# STM32F042G6.net
KiCad netlist of a schematic drawn in Altium Designer
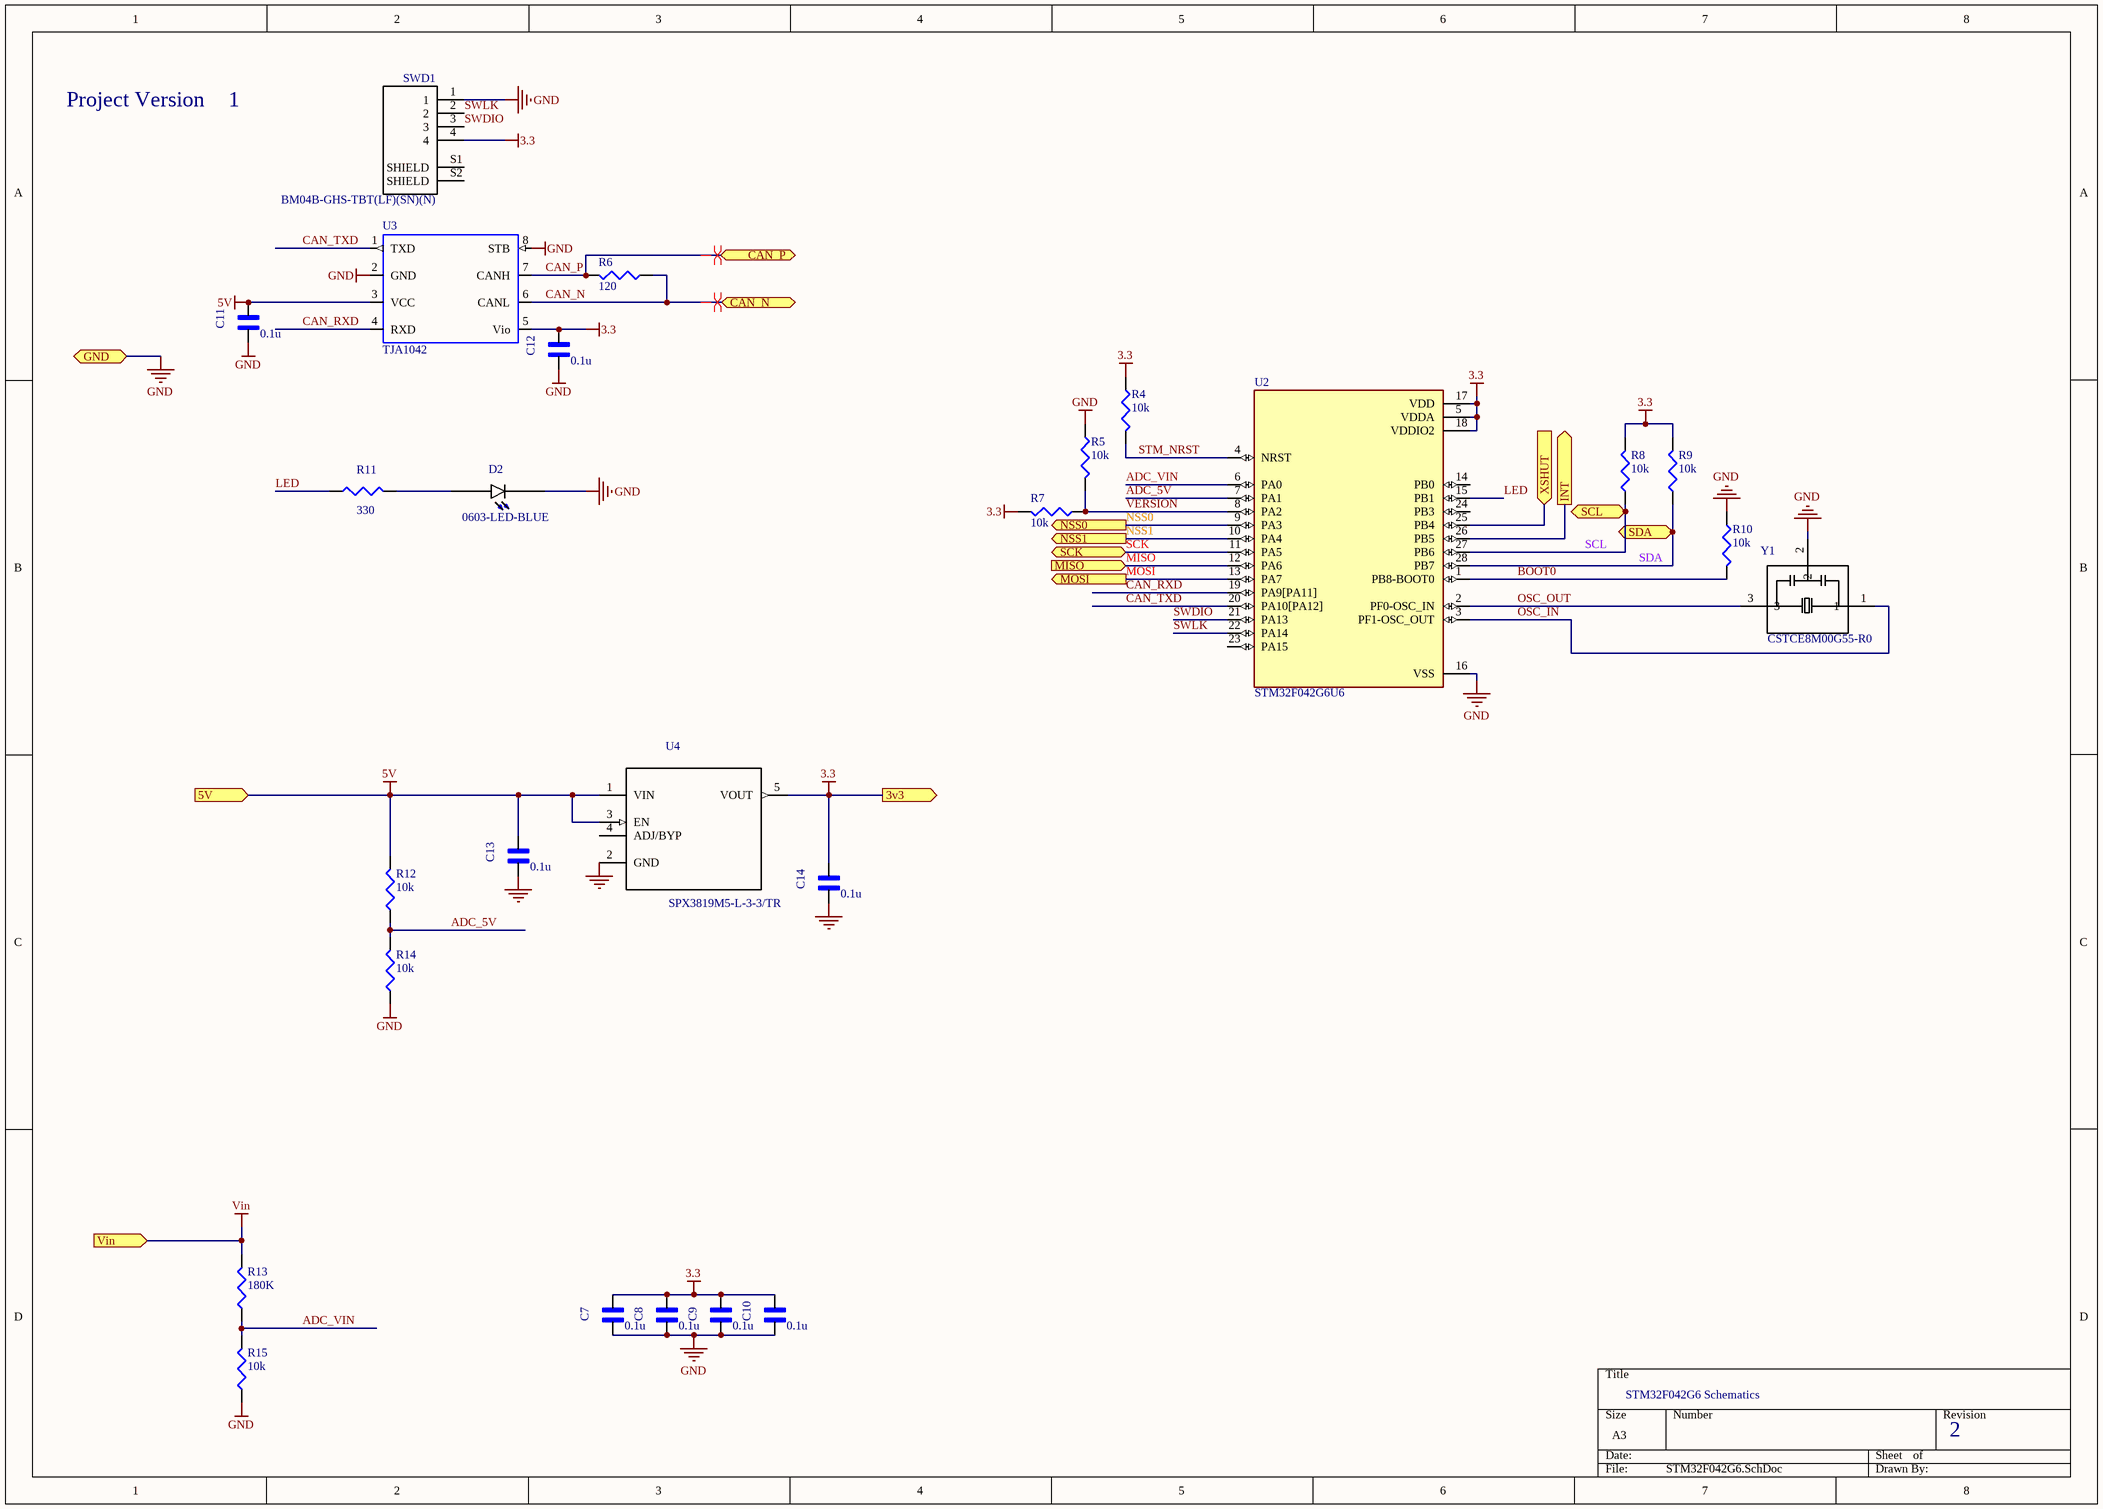
[diagram p0: STM32F042G6.SchDoc]

(export (version "E")
  (design (tool "Eeschema 10.0.6"))
  (components
    (comp (ref "C7")
      (value "0.1u")
      (footprint "*CAPC1608X90")
      (description "Cap Thin Film 0.1uf 50v 0603")
      (fields (field (name "MF") "AVX") (field (name "MP") "GX035C104MAT2-500 or CL10B104JB8NNNC"))
      (libsource (lib "lib") (part "GX035C104MAT2-500"))
    )
    (comp (ref "C8")
      (value "0.1u")
      (footprint "*CAPC1608X90")
      (description "Cap Thin Film 0.1uf 50v 0603")
      (fields (field (name "MF") "AVX") (field (name "MP") "GX035C104MAT2-500 or CL10B104JB8NNNC"))
      (libsource (lib "lib") (part "GX035C104MAT2-500"))
    )
    (comp (ref "C9")
      (value "0.1u")
      (footprint "*CAPC1608X90")
      (description "Cap Thin Film 0.1uf 50v 0603")
      (fields (field (name "MF") "AVX") (field (name "MP") "GX035C104MAT2-500 or CL10B104JB8NNNC"))
      (libsource (lib "lib") (part "GX035C104MAT2-500"))
    )
    (comp (ref "C10")
      (value "0.1u")
      (footprint "*CAPC1608X90")
      (description "Cap Thin Film 0.1uf 50v 0603")
      (fields (field (name "MF") "AVX") (field (name "MP") "GX035C104MAT2-500 or CL10B104JB8NNNC"))
      (libsource (lib "lib") (part "GX035C104MAT2-500"))
    )
    (comp (ref "C11")
      (value "0.1u")
      (footprint "*CAPC1608X90")
      (description "Cap Thin Film 0.1uf 50v 0603")
      (fields (field (name "MF") "AVX") (field (name "MP") "GX035C104MAT2-500 or CL10B104JB8NNNC"))
      (libsource (lib "lib") (part "GX035C104MAT2-500"))
    )
    (comp (ref "C12")
      (value "0.1u")
      (footprint "*CAPC1608X90")
      (description "Cap Thin Film 0.1uf 50v 0603")
      (fields (field (name "MF") "AVX") (field (name "MP") "GX035C104MAT2-500 or CL10B104JB8NNNC"))
      (libsource (lib "lib") (part "GX035C104MAT2-500"))
    )
    (comp (ref "C13")
      (value "0.1u")
      (footprint "*CAPC1608X90")
      (description "Cap Thin Film 0.1uf 50v 0603")
      (fields (field (name "MF") "AVX") (field (name "MP") "GX035C104MAT2-500"))
      (libsource (lib "lib") (part "GX035C104MAT2-500"))
    )
    (comp (ref "C14")
      (value "0.1u")
      (footprint "*CAPC1608X90")
      (description "Cap Thin Film 0.1uf 50v 0603")
      (fields (field (name "MF") "AVX") (field (name "MP") "GX035C104MAT2-500"))
      (libsource (lib "lib") (part "GX035C104MAT2-500"))
    )
    (comp (ref "D2")
      (value "0603-LED-BLUE")
      (footprint "*LEDM1608X80_LTE-C1906R-14(Primary)")
      (description "LED IrLED Chip LED 2-Pin SMD T/R")
      (libsource (lib "lib") (part "LTE-C1906R-14"))
    )
    (comp (ref "R4")
      (value "10k")
      (footprint "J1-0603")
      (description "10 kOhms 1 0.1 W 1 10 W Chip Resistor 0603 1608 Metric Thick Film")
      (fields (field (name "MF") "Yageo or NXP") (field (name "MP") "10K 1% 0603"))
      (libsource (lib "CAN_NODE_MINI") (part "RC0603FR-0710KL"))
    )
    (comp (ref "R5")
      (value "10k")
      (footprint "J1-0603")
      (description "10 kOhms 1 0.1 W 1 10 W Chip Resistor 0603 1608 Metric Thick Film")
      (fields (field (name "MF") "Yageo or NXP") (field (name "MP") "10K 1% 0603"))
      (libsource (lib "CAN_NODE_MINI") (part "RC0603FR-0710KL"))
    )
    (comp (ref "R6")
      (value "120")
      (footprint "J1-0603")
      (description "120 Ohms 1 0.1 W 1 10 W Chip Resistor 0603 1608 Metric Thick Film")
      (fields (field (name "MP") "RC0603FR-07120RL") (field (name "Comment") "Res3"))
      (libsource (lib "Miscellaneous Devices") (part "Res3"))
    )
    (comp (ref "R7")
      (value "10k")
      (footprint "J1-0603")
      (description "10 kOhms 1 0.1 W 1 10 W Chip Resistor 0603 1608 Metric Thick Film")
      (fields (field (name "MF") "Yageo or NXP") (field (name "MP") "10K 1% 0603"))
      (libsource (lib "CAN_NODE_MINI") (part "RC0603FR-0710KL"))
    )
    (comp (ref "R8")
      (value "10k")
      (footprint "J1-0603")
      (description "10 kOhms 1 0.1 W 1 10 W Chip Resistor 0603 1608 Metric Thick Film")
      (fields (field (name "MF") "Yageo or NXP") (field (name "MP") "10K 1% 0603"))
      (libsource (lib "CAN_NODE_MINI") (part "RC0603FR-0710KL"))
    )
    (comp (ref "R9")
      (value "10k")
      (footprint "J1-0603")
      (description "10 kOhms 1 0.1 W 1 10 W Chip Resistor 0603 1608 Metric Thick Film")
      (fields (field (name "MF") "Yageo or NXP") (field (name "MP") "10K 1% 0603"))
      (libsource (lib "CAN_NODE_MINI") (part "RC0603FR-0710KL"))
    )
    (comp (ref "R10")
      (value "10k")
      (footprint "J1-0603")
      (description "10 kOhms 1 0.1 W 1 10 W Chip Resistor 0603 1608 Metric Thick Film")
      (fields (field (name "MF") "Yageo or NXP") (field (name "MP") "10K 1% 0603"))
      (libsource (lib "CAN_NODE_MINI") (part "RC0603FR-0710KL"))
    )
    (comp (ref "R11")
      (value "330")
      (footprint "J1-0603")
      (description "Resistor")
      (fields (field (name "MP") "RC0603FR-07330RL") (field (name "Comment") "Res3"))
      (libsource (lib "Miscellaneous Devices") (part "Res3"))
    )
    (comp (ref "R12")
      (value "10k")
      (footprint "J1-0603")
      (description "10 kOhms 1 0.1 W 1 10 W Chip Resistor 0603 1608 Metric Thick Film")
      (fields (field (name "MF") "Yageo or NXP") (field (name "MP") "10K 1% 0603"))
      (libsource (lib "CAN_NODE_MINI") (part "RC0603FR-0710KL"))
    )
    (comp (ref "R13")
      (value "180K")
      (footprint "J1-0603")
      (description "10 kOhms 1 0.1 W 1 10 W Chip Resistor 0603 1608 Metric Thick Film")
      (fields (field (name "MF") "Yageo or NXP") (field (name "MP") "10K 1% 0603"))
      (libsource (lib "CAN_NODE_MINI") (part "RC0603FR-0710KL"))
    )
    (comp (ref "R14")
      (value "10k")
      (footprint "J1-0603")
      (description "10 kOhms 1 0.1 W 1 10 W Chip Resistor 0603 1608 Metric Thick Film")
      (fields (field (name "MF") "Yageo or NXP") (field (name "MP") "10K 1% 0603"))
      (libsource (lib "CAN_NODE_MINI") (part "RC0603FR-0710KL"))
    )
    (comp (ref "R15")
      (value "10k")
      (footprint "J1-0603")
      (description "10 kOhms 1 0.1 W 1 10 W Chip Resistor 0603 1608 Metric Thick Film")
      (fields (field (name "MF") "Yageo or NXP") (field (name "MP") "10K 1% 0603"))
      (libsource (lib "CAN_NODE_MINI") (part "RC0603FR-0710KL"))
    )
    (comp (ref "SWD1")
      (value "BM04B-GHS-TBT(LF)(SN)(N)")
      (footprint "JST_PAD")
      (description "Conn Shrouded Header HDR 4 POS 1.25mm Solder ST SMD Reel")
      (fields (field (name "MF") "JST Sales") (field (name "MP") "SM04B-GHS-TB(LF)(SN)"))
      (libsource (lib "lib") (part "BM04B-GHS-TBT(LF)(SN)(N)"))
    )
    (comp (ref "U2")
      (value "STM32F042G6U6")
      (footprint "STM32F042G6U6_UFQFPN4x4")
      (description "ARMÂ® CortexÂ®-M0 STM32F0 Microcontroller IC 32-Bit 48MHz 32KB _32K x 8_ FLASH 28-UFQFPN _4x4_")
      (fields (field (name "MF") "STMicroelectronics") (field (name "DESIGNER") "Ehsan Shaghaei"))
      (libsource (lib "lib") (part "STM32F042G6U6"))
    )
    (comp (ref "U3")
      (value "TJA1042")
      (footprint "SOT782-1")
      (description "1/1 Transceiver Half CANbus 8-SO")
      (fields (field (name "MF") "NXP USA"))
      (libsource (lib "lib") (part "TJA1042"))
    )
    (comp (ref "U4")
      (value "SPX3819M5-L-3-3/TR")
      (footprint "*SOT95P280X145-5N")
      (description "Low Dropout Voltage Regulator, Adjustable 0.5A, В±1%, 2.5 to 16 Vin, 5-Pin SOT-23")
      (fields (field (name "MF") "MaxLinear, Inc."))
      (libsource (lib "DC_DC") (part "SPX3819M5-L"))
    )
    (comp (ref "Y1")
      (value "CSTCE8M00G55-R0")
      (footprint "*OSC_CSTCE8M00G55-R0")
      (description "Ceramic Resonator 8MHz ??0.5% _Tol_ ??0.2% _Stability_ 33pF 40Ohm 3-Pin CSMD T/R")
      (fields (field (name "MF") "Murata"))
      (libsource (lib "DC_DC") (part "CSTCE8M00G55-R0"))
    )
  )
  (nets
    (net (code "1") (name "/ADC_5V") (class "Default")
      (node (ref "R12") (pin "1") (pinfunction "1_1") (pintype "passive"))
      (node (ref "R14") (pin "2") (pinfunction "2_2") (pintype "passive"))
      (node (ref "U2") (pin "7") (pinfunction "PA1_7") (pintype "bidirectional"))
    )
    (net (code "2") (name "/ADC_VIN") (class "Default")
      (node (ref "R13") (pin "1") (pinfunction "1_1") (pintype "passive"))
      (node (ref "R15") (pin "2") (pinfunction "2_2") (pintype "passive"))
      (node (ref "U2") (pin "6") (pinfunction "PA0_6") (pintype "bidirectional"))
    )
    (net (code "3") (name "/BOOT0") (class "Default")
      (node (ref "R10") (pin "2") (pinfunction "2_2") (pintype "passive"))
      (node (ref "U2") (pin "1") (pinfunction "PB8-BOOT0_1") (pintype "bidirectional"))
    )
    (net (code "4") (name "/CAN_N") (class "Default")
      (node (ref "R6") (pin "1") (pinfunction "1_1") (pintype "passive"))
      (node (ref "U3") (pin "6") (pinfunction "CANL_6") (pintype "bidirectional"))
    )
    (net (code "5") (name "/CAN_P") (class "Default")
      (node (ref "R6") (pin "2") (pinfunction "2_2") (pintype "passive"))
      (node (ref "U3") (pin "7") (pinfunction "CANH_7") (pintype "bidirectional"))
    )
    (net (code "6") (name "/CAN_RXD") (class "Default")
      (node (ref "U2") (pin "19") (pinfunction "PA9[PA11]_19") (pintype "bidirectional"))
      (node (ref "U3") (pin "4") (pinfunction "RXD_4") (pintype "bidirectional"))
    )
    (net (code "7") (name "/CAN_TXD") (class "Default")
      (node (ref "U2") (pin "20") (pinfunction "PA10[PA12]_20") (pintype "bidirectional"))
      (node (ref "U3") (pin "1") (pinfunction "TXD_1") (pintype "output"))
    )
    (net (code "8") (name "/INT") (class "Default")
      (node (ref "U2") (pin "26") (pinfunction "PB5_26") (pintype "bidirectional"))
    )
    (net (code "9") (name "/LED") (class "Default")
      (node (ref "R11") (pin "1") (pinfunction "1_1") (pintype "passive"))
      (node (ref "U2") (pin "15") (pinfunction "PB1_15") (pintype "bidirectional"))
    )
    (net (code "10") (name "/MISO") (class "Default")
      (node (ref "U2") (pin "12") (pinfunction "PA6_12") (pintype "bidirectional"))
    )
    (net (code "11") (name "/MOSI") (class "Default")
      (node (ref "U2") (pin "13") (pinfunction "PA7_13") (pintype "bidirectional"))
    )
    (net (code "12") (name "/NSS0") (class "Default")
      (node (ref "U2") (pin "9") (pinfunction "PA3_9") (pintype "bidirectional"))
    )
    (net (code "13") (name "/NSS1") (class "Default")
      (node (ref "U2") (pin "10") (pinfunction "PA4_10") (pintype "bidirectional"))
    )
    (net (code "14") (name "/OSC_IN") (class "Default")
      (node (ref "U2") (pin "3") (pinfunction "PF1-OSC_OUT_3") (pintype "bidirectional"))
      (node (ref "Y1") (pin "1") (pinfunction "1_1") (pintype "passive"))
    )
    (net (code "15") (name "/OSC_OUT") (class "Default")
      (node (ref "U2") (pin "2") (pinfunction "PF0-OSC_IN_2") (pintype "bidirectional"))
      (node (ref "Y1") (pin "3") (pinfunction "3_3") (pintype "passive"))
    )
    (net (code "16") (name "/SCK") (class "Default")
      (node (ref "U2") (pin "11") (pinfunction "PA5_11") (pintype "bidirectional"))
    )
    (net (code "17") (name "/SCL") (class "Default")
      (node (ref "R8") (pin "1") (pinfunction "1_1") (pintype "passive"))
      (node (ref "U2") (pin "27") (pinfunction "PB6_27") (pintype "bidirectional"))
    )
    (net (code "18") (name "/SDA") (class "Default")
      (node (ref "R9") (pin "1") (pinfunction "1_1") (pintype "passive"))
      (node (ref "U2") (pin "28") (pinfunction "PB7_28") (pintype "bidirectional"))
    )
    (net (code "19") (name "/STM_NRST") (class "Default")
      (node (ref "R4") (pin "2") (pinfunction "2_2") (pintype "passive"))
      (node (ref "U2") (pin "4") (pinfunction "NRST_4") (pintype "bidirectional"))
    )
    (net (code "20") (name "/SWDIO") (class "Default")
      (node (ref "SWD1") (pin "3") (pinfunction "3_3") (pintype "passive"))
      (node (ref "U2") (pin "21") (pinfunction "PA13_21") (pintype "bidirectional"))
    )
    (net (code "21") (name "/SWLK") (class "Default")
      (node (ref "SWD1") (pin "2") (pinfunction "2_2") (pintype "passive"))
      (node (ref "U2") (pin "22") (pinfunction "PA14_22") (pintype "bidirectional"))
    )
    (net (code "22") (name "/VERSION") (class "Default")
      (node (ref "R5") (pin "2") (pinfunction "2_2") (pintype "passive"))
      (node (ref "R7") (pin "1") (pinfunction "1_1") (pintype "passive"))
      (node (ref "U2") (pin "8") (pinfunction "PA2_8") (pintype "bidirectional"))
    )
    (net (code "23") (name "/XSHUT") (class "Default")
      (node (ref "U2") (pin "25") (pinfunction "PB4_25") (pintype "bidirectional"))
    )
    (net (code "24") (name "3.3") (class "Default")
      (node (ref "C10") (pin "1") (pinfunction "1_1") (pintype "passive"))
      (node (ref "C12") (pin "1") (pinfunction "1_1") (pintype "passive"))
      (node (ref "C14") (pin "1") (pinfunction "1_1") (pintype "passive"))
      (node (ref "C7") (pin "1") (pinfunction "1_1") (pintype "passive"))
      (node (ref "C8") (pin "1") (pinfunction "1_1") (pintype "passive"))
      (node (ref "C9") (pin "1") (pinfunction "1_1") (pintype "passive"))
      (node (ref "R4") (pin "1") (pinfunction "1_1") (pintype "passive"))
      (node (ref "R7") (pin "2") (pinfunction "2_2") (pintype "passive"))
      (node (ref "R8") (pin "2") (pinfunction "2_2") (pintype "passive"))
      (node (ref "R9") (pin "2") (pinfunction "2_2") (pintype "passive"))
      (node (ref "SWD1") (pin "4") (pinfunction "4_4") (pintype "passive"))
      (node (ref "U2") (pin "17") (pinfunction "VDD_17") (pintype "power_in"))
      (node (ref "U2") (pin "18") (pinfunction "VDDIO2_18") (pintype "power_in"))
      (node (ref "U2") (pin "5") (pinfunction "VDDA_5") (pintype "power_in"))
      (node (ref "U3") (pin "5") (pinfunction "Vio_5") (pintype "power_in"))
      (node (ref "U4") (pin "5") (pinfunction "VOUT_5") (pintype "output"))
    )
    (net (code "25") (name "5V") (class "Default")
      (node (ref "C11") (pin "1") (pinfunction "1_1") (pintype "passive"))
      (node (ref "C13") (pin "1") (pinfunction "1_1") (pintype "passive"))
      (node (ref "R12") (pin "2") (pinfunction "2_2") (pintype "passive"))
      (node (ref "U3") (pin "3") (pinfunction "VCC_3") (pintype "power_in"))
      (node (ref "U4") (pin "1") (pinfunction "VIN_1") (pintype "power_in"))
      (node (ref "U4") (pin "3") (pinfunction "EN_3") (pintype "input"))
    )
    (net (code "26") (name "GND") (class "Default")
      (node (ref "C10") (pin "2") (pinfunction "2_2") (pintype "passive"))
      (node (ref "C11") (pin "2") (pinfunction "2_2") (pintype "passive"))
      (node (ref "C12") (pin "2") (pinfunction "2_2") (pintype "passive"))
      (node (ref "C13") (pin "2") (pinfunction "2_2") (pintype "passive"))
      (node (ref "C14") (pin "2") (pinfunction "2_2") (pintype "passive"))
      (node (ref "C7") (pin "2") (pinfunction "2_2") (pintype "passive"))
      (node (ref "C8") (pin "2") (pinfunction "2_2") (pintype "passive"))
      (node (ref "C9") (pin "2") (pinfunction "2_2") (pintype "passive"))
      (node (ref "D2") (pin "C") (pinfunction "C_C") (pintype "passive"))
      (node (ref "R10") (pin "1") (pinfunction "1_1") (pintype "passive"))
      (node (ref "R14") (pin "1") (pinfunction "1_1") (pintype "passive"))
      (node (ref "R15") (pin "1") (pinfunction "1_1") (pintype "passive"))
      (node (ref "R5") (pin "1") (pinfunction "1_1") (pintype "passive"))
      (node (ref "SWD1") (pin "1") (pinfunction "1_1") (pintype "passive"))
      (node (ref "U2") (pin "16") (pinfunction "VSS_16") (pintype "power_in"))
      (node (ref "U3") (pin "2") (pinfunction "GND_2") (pintype "power_in"))
      (node (ref "U3") (pin "8") (pinfunction "STB_8") (pintype "input"))
      (node (ref "U4") (pin "2") (pinfunction "GND_2") (pintype "passive"))
      (node (ref "Y1") (pin "2") (pinfunction "2_2") (pintype "power_in"))
    )
    (net (code "27") (name "Net-(D2-PadA)") (class "Default")
      (node (ref "D2") (pin "A") (pinfunction "A_A") (pintype "passive"))
      (node (ref "R11") (pin "2") (pinfunction "2_2") (pintype "passive"))
    )
    (net (code "28") (name "Vin") (class "Default")
      (node (ref "R13") (pin "2") (pinfunction "2_2") (pintype "passive"))
    )
    (net (code "29") (name "unconnected-(SWD1-SHIELD-PadS1)") (class "Default")
      (node (ref "SWD1") (pin "S1") (pinfunction "SHIELD_S1") (pintype "passive"))
    )
    (net (code "30") (name "unconnected-(SWD1-SHIELD-PadS2)") (class "Default")
      (node (ref "SWD1") (pin "S2") (pinfunction "SHIELD_S2") (pintype "passive"))
    )
    (net (code "31") (name "unconnected-(U2-PA15-Pad23)") (class "Default")
      (node (ref "U2") (pin "23") (pinfunction "PA15_23") (pintype "bidirectional"))
    )
    (net (code "32") (name "unconnected-(U2-PB0-Pad14)") (class "Default")
      (node (ref "U2") (pin "14") (pinfunction "PB0_14") (pintype "bidirectional"))
    )
    (net (code "33") (name "unconnected-(U2-PB3-Pad24)") (class "Default")
      (node (ref "U2") (pin "24") (pinfunction "PB3_24") (pintype "bidirectional"))
    )
    (net (code "34") (name "unconnected-(U4-ADJ{slash}BYP-Pad4)") (class "Default")
      (node (ref "U4") (pin "4") (pinfunction "ADJ/BYP_4") (pintype "passive"))
    )
  )
)
